# SCH_Macropad_2024-08-07.net
KiCad netlist of a schematic drawn in EasyEDA
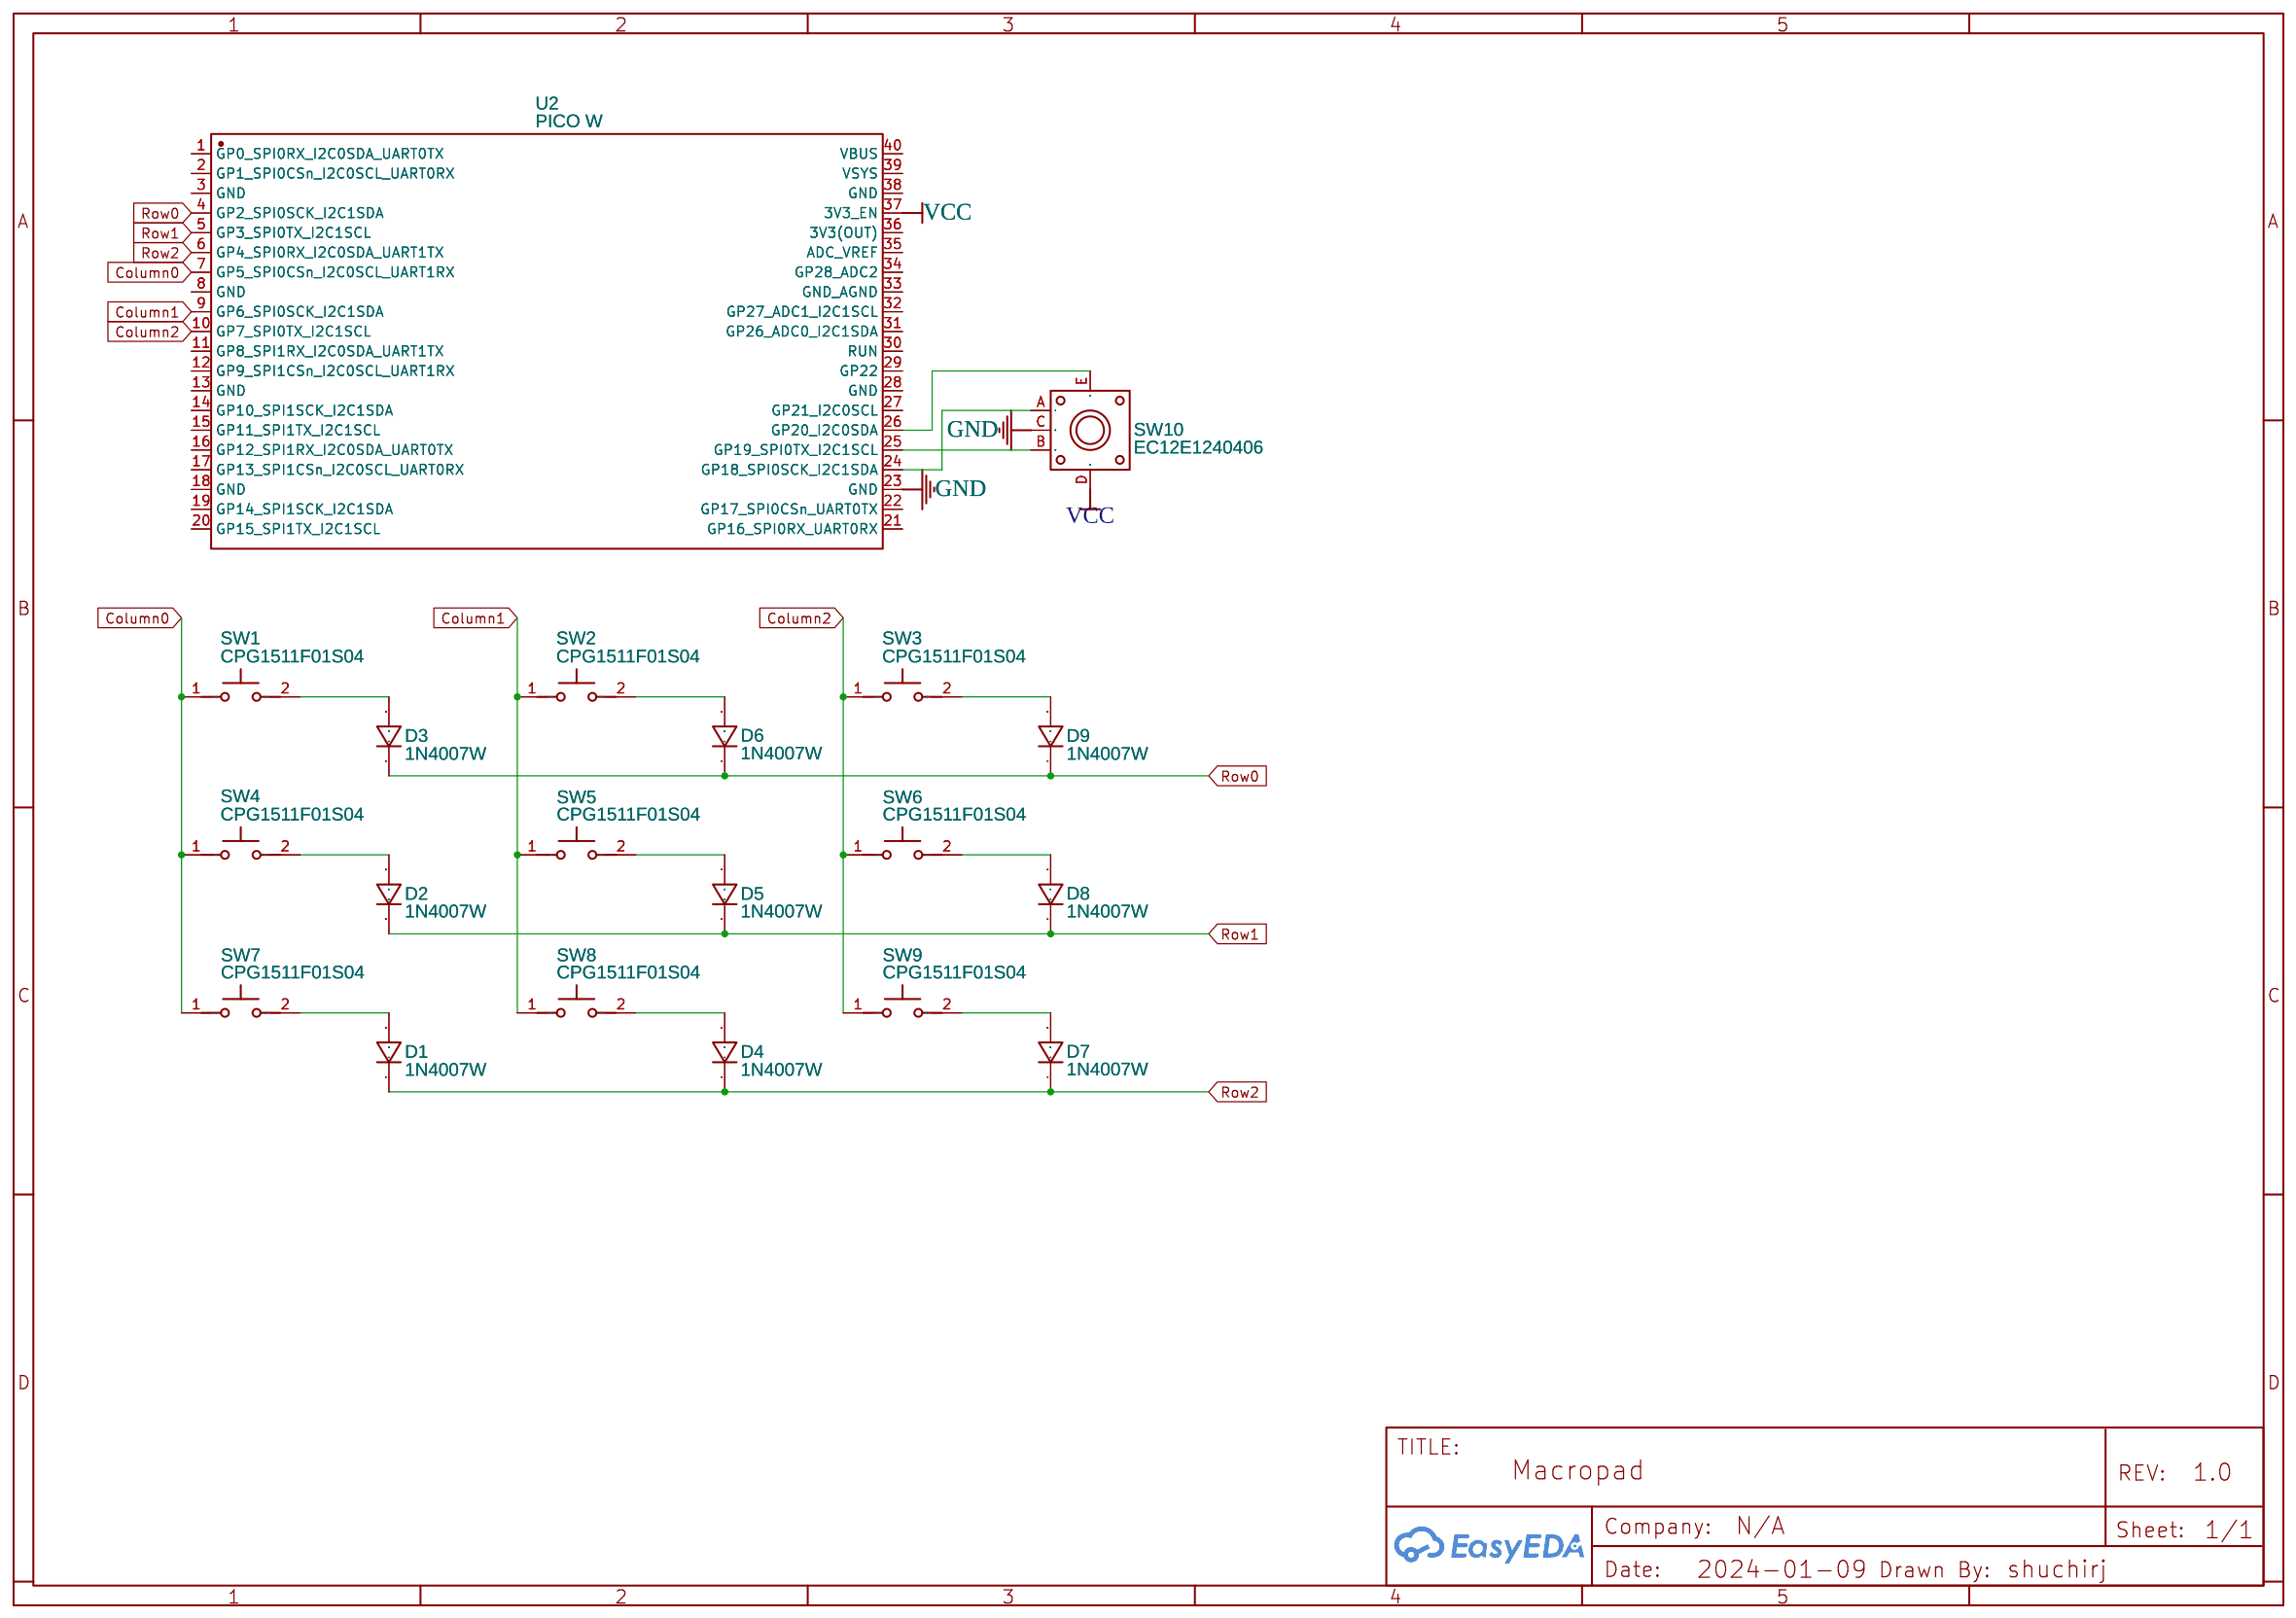
[diagram p0: schematic sheet]

(export (version "E")
  (design (tool "Eeschema 10.0.6"))
  (components
    (comp (ref "D1")
      (value "1N4007W")
      (fields (field (name "Manufacturer") "BLUE ROCKET"))
      (libsource (lib "") (part "1N4007W"))
    )
    (comp (ref "D2")
      (value "1N4007W")
      (fields (field (name "Manufacturer") "BLUE ROCKET"))
      (libsource (lib "") (part "1N4007W"))
    )
    (comp (ref "D3")
      (value "1N4007W")
      (fields (field (name "Manufacturer") "BLUE ROCKET"))
      (libsource (lib "") (part "1N4007W"))
    )
    (comp (ref "D4")
      (value "1N4007W")
      (fields (field (name "Manufacturer") "BLUE ROCKET"))
      (libsource (lib "") (part "1N4007W"))
    )
    (comp (ref "D5")
      (value "1N4007W")
      (fields (field (name "Manufacturer") "BLUE ROCKET"))
      (libsource (lib "") (part "1N4007W"))
    )
    (comp (ref "D6")
      (value "1N4007W")
      (fields (field (name "Manufacturer") "BLUE ROCKET"))
      (libsource (lib "") (part "1N4007W"))
    )
    (comp (ref "D7")
      (value "1N4007W")
      (fields (field (name "Manufacturer") "BLUE ROCKET"))
      (libsource (lib "") (part "1N4007W"))
    )
    (comp (ref "D8")
      (value "1N4007W")
      (fields (field (name "Manufacturer") "BLUE ROCKET"))
      (libsource (lib "") (part "1N4007W"))
    )
    (comp (ref "D9")
      (value "1N4007W")
      (fields (field (name "Manufacturer") "BLUE ROCKET"))
      (libsource (lib "") (part "1N4007W"))
    )
    (comp (ref "SW1")
      (value "CPG1511F01S04")
      (fields (field (name "Manufacturer") "Kailh"))
      (libsource (lib "") (part "CPG1511F01S04"))
    )
    (comp (ref "SW2")
      (value "CPG1511F01S04")
      (fields (field (name "Manufacturer") "Kailh"))
      (libsource (lib "") (part "CPG1511F01S04"))
    )
    (comp (ref "SW3")
      (value "CPG1511F01S04")
      (fields (field (name "Manufacturer") "Kailh"))
      (libsource (lib "") (part "CPG1511F01S04"))
    )
    (comp (ref "SW4")
      (value "CPG1511F01S04")
      (fields (field (name "Manufacturer") "Kailh"))
      (libsource (lib "") (part "CPG1511F01S04"))
    )
    (comp (ref "SW5")
      (value "CPG1511F01S04")
      (fields (field (name "Manufacturer") "Kailh"))
      (libsource (lib "") (part "CPG1511F01S04"))
    )
    (comp (ref "SW6")
      (value "CPG1511F01S04")
      (fields (field (name "Manufacturer") "Kailh"))
      (libsource (lib "") (part "CPG1511F01S04"))
    )
    (comp (ref "SW7")
      (value "CPG1511F01S04")
      (fields (field (name "Manufacturer") "Kailh"))
      (libsource (lib "") (part "CPG1511F01S04"))
    )
    (comp (ref "SW8")
      (value "CPG1511F01S04")
      (fields (field (name "Manufacturer") "Kailh"))
      (libsource (lib "") (part "CPG1511F01S04"))
    )
    (comp (ref "SW9")
      (value "CPG1511F01S04")
      (fields (field (name "Manufacturer") "Kailh"))
      (libsource (lib "") (part "CPG1511F01S04"))
    )
    (comp (ref "SW10")
      (value "EC12E1240406")
      (fields (field (name "Manufacturer") "ALPS Electric"))
      (libsource (lib "") (part "EC12E1240406"))
    )
    (comp (ref "U2")
      (value "PICO W")
      (fields (field (name "Manufacturer") "Raspberry Pi(树莓派)"))
      (libsource (lib "") (part "PICO W"))
    )
  )
  (nets
    (net (code "1") (name "Column0") (class "Default")
      (node (ref "SW1") (pin "1") (pinfunction "1_1") (pintype "unspecified"))
      (node (ref "SW4") (pin "1") (pinfunction "1_1") (pintype "unspecified"))
      (node (ref "SW7") (pin "1") (pinfunction "1_1") (pintype "unspecified"))
      (node (ref "U2") (pin "7") (pinfunction "GP5_SPI0CSn_I2C0SCL_UART1RX_7") (pintype "unspecified"))
    )
    (net (code "2") (name "Column1") (class "Default")
      (node (ref "SW2") (pin "1") (pinfunction "1_1") (pintype "unspecified"))
      (node (ref "SW5") (pin "1") (pinfunction "1_1") (pintype "unspecified"))
      (node (ref "SW8") (pin "1") (pinfunction "1_1") (pintype "unspecified"))
      (node (ref "U2") (pin "9") (pinfunction "GP6_SPI0SCK_I2C1SDA_9") (pintype "unspecified"))
    )
    (net (code "3") (name "Column2") (class "Default")
      (node (ref "SW3") (pin "1") (pinfunction "1_1") (pintype "unspecified"))
      (node (ref "SW6") (pin "1") (pinfunction "1_1") (pintype "unspecified"))
      (node (ref "SW9") (pin "1") (pinfunction "1_1") (pintype "unspecified"))
      (node (ref "U2") (pin "10") (pinfunction "GP7_SPI0TX_I2C1SCL_10") (pintype "unspecified"))
    )
    (net (code "4") (name "GND") (class "Default")
      (node (ref "SW10") (pin "C") (pinfunction "C_C") (pintype "unspecified"))
      (node (ref "U2") (pin "23") (pinfunction "GND_23") (pintype "unspecified"))
    )
    (net (code "5") (name "Net-(D1-Pad2)") (class "Default")
      (node (ref "D1") (pin "2") (pinfunction "2_2") (pintype "unspecified"))
      (node (ref "SW7") (pin "2") (pinfunction "2_2") (pintype "unspecified"))
    )
    (net (code "6") (name "Net-(D2-Pad2)") (class "Default")
      (node (ref "D2") (pin "2") (pinfunction "2_2") (pintype "unspecified"))
      (node (ref "SW4") (pin "2") (pinfunction "2_2") (pintype "unspecified"))
    )
    (net (code "7") (name "Net-(D3-Pad2)") (class "Default")
      (node (ref "D3") (pin "2") (pinfunction "2_2") (pintype "unspecified"))
      (node (ref "SW1") (pin "2") (pinfunction "2_2") (pintype "unspecified"))
    )
    (net (code "8") (name "Net-(D4-Pad2)") (class "Default")
      (node (ref "D4") (pin "2") (pinfunction "2_2") (pintype "unspecified"))
      (node (ref "SW8") (pin "2") (pinfunction "2_2") (pintype "unspecified"))
    )
    (net (code "9") (name "Net-(D5-Pad2)") (class "Default")
      (node (ref "D5") (pin "2") (pinfunction "2_2") (pintype "unspecified"))
      (node (ref "SW5") (pin "2") (pinfunction "2_2") (pintype "unspecified"))
    )
    (net (code "10") (name "Net-(D6-Pad2)") (class "Default")
      (node (ref "D6") (pin "2") (pinfunction "2_2") (pintype "unspecified"))
      (node (ref "SW2") (pin "2") (pinfunction "2_2") (pintype "unspecified"))
    )
    (net (code "11") (name "Net-(D7-Pad2)") (class "Default")
      (node (ref "D7") (pin "2") (pinfunction "2_2") (pintype "unspecified"))
      (node (ref "SW9") (pin "2") (pinfunction "2_2") (pintype "unspecified"))
    )
    (net (code "12") (name "Net-(D8-Pad2)") (class "Default")
      (node (ref "D8") (pin "2") (pinfunction "2_2") (pintype "unspecified"))
      (node (ref "SW6") (pin "2") (pinfunction "2_2") (pintype "unspecified"))
    )
    (net (code "13") (name "Net-(D9-Pad2)") (class "Default")
      (node (ref "D9") (pin "2") (pinfunction "2_2") (pintype "unspecified"))
      (node (ref "SW3") (pin "2") (pinfunction "2_2") (pintype "unspecified"))
    )
    (net (code "14") (name "Net-(U2-GP18_SPI0SCK_I2C1SDA)") (class "Default")
      (node (ref "SW10") (pin "A") (pinfunction "A_A") (pintype "unspecified"))
      (node (ref "U2") (pin "24") (pinfunction "GP18_SPI0SCK_I2C1SDA_24") (pintype "unspecified"))
    )
    (net (code "15") (name "Net-(U2-GP19_SPI0TX_I2C1SCL)") (class "Default")
      (node (ref "SW10") (pin "B") (pinfunction "B_B") (pintype "unspecified"))
      (node (ref "U2") (pin "25") (pinfunction "GP19_SPI0TX_I2C1SCL_25") (pintype "unspecified"))
    )
    (net (code "16") (name "Net-(U2-GP20_I2C0SDA)") (class "Default")
      (node (ref "SW10") (pin "E") (pinfunction "E_E") (pintype "unspecified"))
      (node (ref "U2") (pin "26") (pinfunction "GP20_I2C0SDA_26") (pintype "unspecified"))
    )
    (net (code "17") (name "Row0") (class "Default")
      (node (ref "D3") (pin "1") (pinfunction "1_1") (pintype "unspecified"))
      (node (ref "D6") (pin "1") (pinfunction "1_1") (pintype "unspecified"))
      (node (ref "D9") (pin "1") (pinfunction "1_1") (pintype "unspecified"))
      (node (ref "U2") (pin "4") (pinfunction "GP2_SPI0SCK_I2C1SDA_4") (pintype "unspecified"))
    )
    (net (code "18") (name "Row1") (class "Default")
      (node (ref "D2") (pin "1") (pinfunction "1_1") (pintype "unspecified"))
      (node (ref "D5") (pin "1") (pinfunction "1_1") (pintype "unspecified"))
      (node (ref "D8") (pin "1") (pinfunction "1_1") (pintype "unspecified"))
      (node (ref "U2") (pin "5") (pinfunction "GP3_SPI0TX_I2C1SCL_5") (pintype "unspecified"))
    )
    (net (code "19") (name "Row2") (class "Default")
      (node (ref "D1") (pin "1") (pinfunction "1_1") (pintype "unspecified"))
      (node (ref "D4") (pin "1") (pinfunction "1_1") (pintype "unspecified"))
      (node (ref "D7") (pin "1") (pinfunction "1_1") (pintype "unspecified"))
      (node (ref "U2") (pin "6") (pinfunction "GP4_SPI0RX_I2C0SDA_UART1TX_6") (pintype "unspecified"))
    )
    (net (code "20") (name "VCC") (class "Default")
      (node (ref "SW10") (pin "D") (pinfunction "D_D") (pintype "unspecified"))
      (node (ref "U2") (pin "37") (pinfunction "3V3_EN_37") (pintype "unspecified"))
    )
    (net (code "21") (name "unconnected-(U2-3V3(OUT)-Pad36)") (class "Default")
      (node (ref "U2") (pin "36") (pinfunction "3V3(OUT)_36") (pintype "unspecified"))
    )
    (net (code "22") (name "unconnected-(U2-ADC_VREF-Pad35)") (class "Default")
      (node (ref "U2") (pin "35") (pinfunction "ADC_VREF_35") (pintype "unspecified"))
    )
    (net (code "23") (name "unconnected-(U2-GND-Pad3)") (class "Default")
      (node (ref "U2") (pin "3") (pinfunction "GND_3") (pintype "unspecified"))
    )
    (net (code "24") (name "unconnected-(U2-GND-Pad8)") (class "Default")
      (node (ref "U2") (pin "8") (pinfunction "GND_8") (pintype "unspecified"))
    )
    (net (code "25") (name "unconnected-(U2-GND-Pad13)") (class "Default")
      (node (ref "U2") (pin "13") (pinfunction "GND_13") (pintype "unspecified"))
    )
    (net (code "26") (name "unconnected-(U2-GND-Pad18)") (class "Default")
      (node (ref "U2") (pin "18") (pinfunction "GND_18") (pintype "unspecified"))
    )
    (net (code "27") (name "unconnected-(U2-GND-Pad28)") (class "Default")
      (node (ref "U2") (pin "28") (pinfunction "GND_28") (pintype "unspecified"))
    )
    (net (code "28") (name "unconnected-(U2-GND-Pad38)") (class "Default")
      (node (ref "U2") (pin "38") (pinfunction "GND_38") (pintype "unspecified"))
    )
    (net (code "29") (name "unconnected-(U2-GND_AGND-Pad33)") (class "Default")
      (node (ref "U2") (pin "33") (pinfunction "GND_AGND_33") (pintype "unspecified"))
    )
    (net (code "30") (name "unconnected-(U2-GP0_SPI0RX_I2C0SDA_UART0TX-Pad1)") (class "Default")
      (node (ref "U2") (pin "1") (pinfunction "GP0_SPI0RX_I2C0SDA_UART0TX_1") (pintype "unspecified"))
    )
    (net (code "31") (name "unconnected-(U2-GP1_SPI0CSn_I2C0SCL_UART0RX-Pad2)") (class "Default")
      (node (ref "U2") (pin "2") (pinfunction "GP1_SPI0CSn_I2C0SCL_UART0RX_2") (pintype "unspecified"))
    )
    (net (code "32") (name "unconnected-(U2-GP8_SPI1RX_I2C0SDA_UART1TX-Pad11)") (class "Default")
      (node (ref "U2") (pin "11") (pinfunction "GP8_SPI1RX_I2C0SDA_UART1TX_11") (pintype "unspecified"))
    )
    (net (code "33") (name "unconnected-(U2-GP9_SPI1CSn_I2C0SCL_UART1RX-Pad12)") (class "Default")
      (node (ref "U2") (pin "12") (pinfunction "GP9_SPI1CSn_I2C0SCL_UART1RX_12") (pintype "unspecified"))
    )
    (net (code "34") (name "unconnected-(U2-GP10_SPI1SCK_I2C1SDA-Pad14)") (class "Default")
      (node (ref "U2") (pin "14") (pinfunction "GP10_SPI1SCK_I2C1SDA_14") (pintype "unspecified"))
    )
    (net (code "35") (name "unconnected-(U2-GP11_SPI1TX_I2C1SCL-Pad15)") (class "Default")
      (node (ref "U2") (pin "15") (pinfunction "GP11_SPI1TX_I2C1SCL_15") (pintype "unspecified"))
    )
    (net (code "36") (name "unconnected-(U2-GP12_SPI1RX_I2C0SDA_UART0TX-Pad16)") (class "Default")
      (node (ref "U2") (pin "16") (pinfunction "GP12_SPI1RX_I2C0SDA_UART0TX_16") (pintype "unspecified"))
    )
    (net (code "37") (name "unconnected-(U2-GP13_SPI1CSn_I2C0SCL_UART0RX-Pad17)") (class "Default")
      (node (ref "U2") (pin "17") (pinfunction "GP13_SPI1CSn_I2C0SCL_UART0RX_17") (pintype "unspecified"))
    )
    (net (code "38") (name "unconnected-(U2-GP14_SPI1SCK_I2C1SDA-Pad19)") (class "Default")
      (node (ref "U2") (pin "19") (pinfunction "GP14_SPI1SCK_I2C1SDA_19") (pintype "unspecified"))
    )
    (net (code "39") (name "unconnected-(U2-GP15_SPI1TX_I2C1SCL-Pad20)") (class "Default")
      (node (ref "U2") (pin "20") (pinfunction "GP15_SPI1TX_I2C1SCL_20") (pintype "unspecified"))
    )
    (net (code "40") (name "unconnected-(U2-GP16_SPI0RX_UART0RX-Pad21)") (class "Default")
      (node (ref "U2") (pin "21") (pinfunction "GP16_SPI0RX_UART0RX_21") (pintype "unspecified"))
    )
    (net (code "41") (name "unconnected-(U2-GP17_SPI0CSn_UART0TX-Pad22)") (class "Default")
      (node (ref "U2") (pin "22") (pinfunction "GP17_SPI0CSn_UART0TX_22") (pintype "unspecified"))
    )
    (net (code "42") (name "unconnected-(U2-GP21_I2C0SCL-Pad27)") (class "Default")
      (node (ref "U2") (pin "27") (pinfunction "GP21_I2C0SCL_27") (pintype "unspecified"))
    )
    (net (code "43") (name "unconnected-(U2-GP22-Pad29)") (class "Default")
      (node (ref "U2") (pin "29") (pinfunction "GP22_29") (pintype "unspecified"))
    )
    (net (code "44") (name "unconnected-(U2-GP26_ADC0_I2C1SDA-Pad31)") (class "Default")
      (node (ref "U2") (pin "31") (pinfunction "GP26_ADC0_I2C1SDA_31") (pintype "unspecified"))
    )
    (net (code "45") (name "unconnected-(U2-GP27_ADC1_I2C1SCL-Pad32)") (class "Default")
      (node (ref "U2") (pin "32") (pinfunction "GP27_ADC1_I2C1SCL_32") (pintype "unspecified"))
    )
    (net (code "46") (name "unconnected-(U2-GP28_ADC2-Pad34)") (class "Default")
      (node (ref "U2") (pin "34") (pinfunction "GP28_ADC2_34") (pintype "unspecified"))
    )
    (net (code "47") (name "unconnected-(U2-RUN-Pad30)") (class "Default")
      (node (ref "U2") (pin "30") (pinfunction "RUN_30") (pintype "unspecified"))
    )
    (net (code "48") (name "unconnected-(U2-VBUS-Pad40)") (class "Default")
      (node (ref "U2") (pin "40") (pinfunction "VBUS_40") (pintype "unspecified"))
    )
    (net (code "49") (name "unconnected-(U2-VSYS-Pad39)") (class "Default")
      (node (ref "U2") (pin "39") (pinfunction "VSYS_39") (pintype "unspecified"))
    )
  )
)
